# RelayExtension.net
KiCad netlist of a schematic drawn in Altium Designer
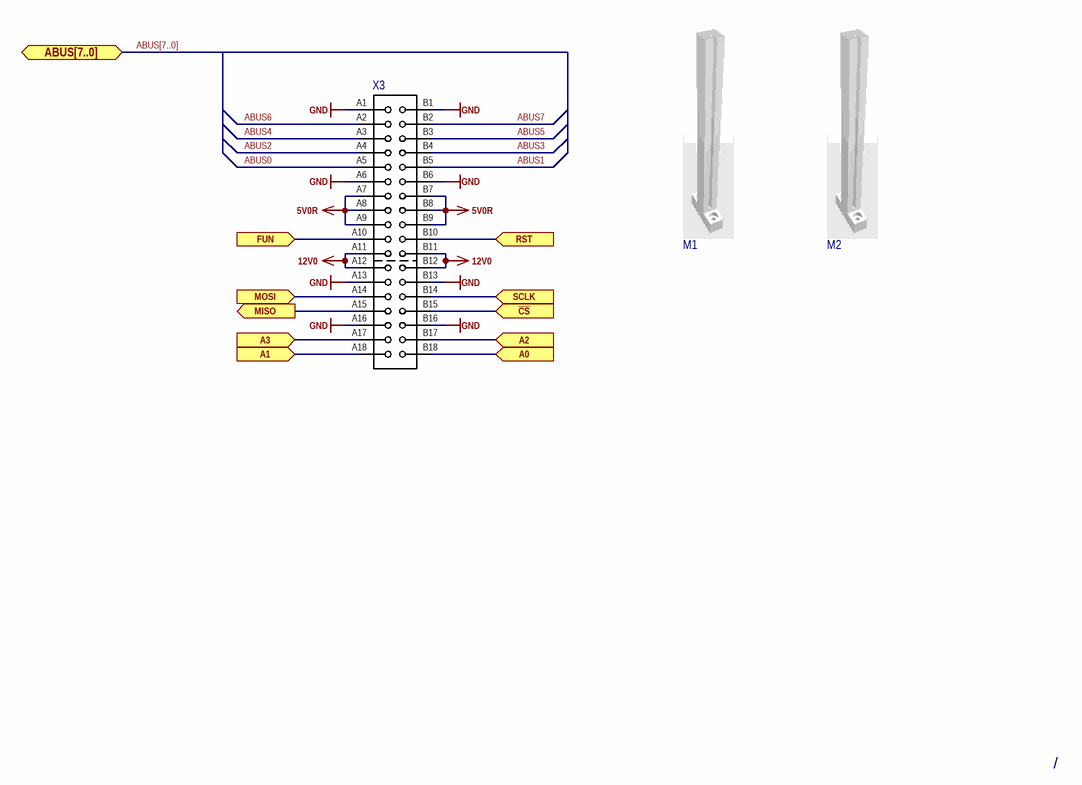
[diagram p0: RelayExtension.SchDoc]

(export (version "E")
  (design (tool "Eeschema 10.0.6"))
  (components
    (comp (ref "M1")
      (value "M")
      (footprint "Support Post")
      (description "Support Post")
      (fields (field (name "13. CREATED DATE/NAME") "??? / Hören"))
      (libsource (lib "PCB-Tester-Board") (part "Support Post"))
    )
    (comp (ref "M2")
      (value "M")
      (footprint "Support Post")
      (description "Support Post")
      (fields (field (name "13. CREATED DATE/NAME") "??? / Hören"))
      (libsource (lib "PCB-Tester-Board") (part "Support Post"))
    )
    (comp (ref "X3")
      (value "X")
      (footprint "PCIE-036-02-F-D-TH")
      (description "CONN PCI EXP FMALE 36POS 0.039")
      (fields
        (field (name "02. DISTRIBUTOR PART NUMBER") "SAM10625-ND")
        (field (name "07. MANUFACTURER  PART NUMBER") "PCIE-036-02-F-D-TH")
        (field (name "13. CREATED DATE/NAME") "??? / Hören")
      )
      (libsource (lib "Connectors") (part "PCIE-036-02-F-D-TH"))
    )
  )
  (nets
    (net (code "1") (name "/A0") (class "Default")
      (node (ref "X3") (pin "B18") (pinfunction "B18_B18") (pintype "passive"))
    )
    (net (code "2") (name "/A1") (class "Default")
      (node (ref "X3") (pin "A18") (pinfunction "A18_A18") (pintype "passive"))
    )
    (net (code "3") (name "/A2") (class "Default")
      (node (ref "X3") (pin "B17") (pinfunction "B17_B17") (pintype "passive"))
    )
    (net (code "4") (name "/A3") (class "Default")
      (node (ref "X3") (pin "A17") (pinfunction "A17_A17") (pintype "passive"))
    )
    (net (code "5") (name "/ABUS0") (class "Default")
      (node (ref "X3") (pin "A5") (pinfunction "A5_A5") (pintype "passive"))
    )
    (net (code "6") (name "/ABUS1") (class "Default")
      (node (ref "X3") (pin "B5") (pinfunction "B5_B5") (pintype "passive"))
    )
    (net (code "7") (name "/ABUS2") (class "Default")
      (node (ref "X3") (pin "A4") (pinfunction "A4_A4") (pintype "passive"))
    )
    (net (code "8") (name "/ABUS3") (class "Default")
      (node (ref "X3") (pin "B4") (pinfunction "B4_B4") (pintype "passive"))
    )
    (net (code "9") (name "/ABUS4") (class "Default")
      (node (ref "X3") (pin "A3") (pinfunction "A3_A3") (pintype "passive"))
    )
    (net (code "10") (name "/ABUS5") (class "Default")
      (node (ref "X3") (pin "B3") (pinfunction "B3_B3") (pintype "passive"))
    )
    (net (code "11") (name "/ABUS6") (class "Default")
      (node (ref "X3") (pin "A2") (pinfunction "A2_A2") (pintype "passive"))
    )
    (net (code "12") (name "/ABUS7") (class "Default")
      (node (ref "X3") (pin "B2") (pinfunction "B2_B2") (pintype "passive"))
    )
    (net (code "14") (name "/CS") (class "Default")
      (node (ref "X3") (pin "B15") (pinfunction "B15_B15") (pintype "passive"))
    )
    (net (code "15") (name "/FUN") (class "Default")
      (node (ref "X3") (pin "A10") (pinfunction "A10_A10") (pintype "passive"))
    )
    (net (code "16") (name "/MISO") (class "Default")
      (node (ref "X3") (pin "A15") (pinfunction "A15_A15") (pintype "passive"))
    )
    (net (code "17") (name "/MOSI") (class "Default")
      (node (ref "X3") (pin "A14") (pinfunction "A14_A14") (pintype "passive"))
    )
    (net (code "18") (name "/RST") (class "Default")
      (node (ref "X3") (pin "B10") (pinfunction "B10_B10") (pintype "passive"))
    )
    (net (code "19") (name "/SCLK") (class "Default")
      (node (ref "X3") (pin "B14") (pinfunction "B14_B14") (pintype "passive"))
    )
    (net (code "20") (name "5V0R") (class "Default")
      (node (ref "X3") (pin "A7") (pinfunction "A7_A7") (pintype "passive"))
      (node (ref "X3") (pin "A8") (pinfunction "A8_A8") (pintype "passive"))
      (node (ref "X3") (pin "A9") (pinfunction "A9_A9") (pintype "passive"))
      (node (ref "X3") (pin "B7") (pinfunction "B7_B7") (pintype "passive"))
      (node (ref "X3") (pin "B8") (pinfunction "B8_B8") (pintype "passive"))
      (node (ref "X3") (pin "B9") (pinfunction "B9_B9") (pintype "passive"))
    )
    (net (code "21") (name "12V0") (class "Default")
      (node (ref "X3") (pin "A11") (pinfunction "A11_A11") (pintype "passive"))
      (node (ref "X3") (pin "A12") (pinfunction "A12_A12") (pintype "passive"))
      (node (ref "X3") (pin "B11") (pinfunction "B11_B11") (pintype "passive"))
      (node (ref "X3") (pin "B12") (pinfunction "B12_B12") (pintype "passive"))
    )
    (net (code "22") (name "GND") (class "Default")
      (node (ref "X3") (pin "A1") (pinfunction "A1_A1") (pintype "passive"))
      (node (ref "X3") (pin "A13") (pinfunction "A13_A13") (pintype "passive"))
      (node (ref "X3") (pin "A16") (pinfunction "A16_A16") (pintype "passive"))
      (node (ref "X3") (pin "A6") (pinfunction "A6_A6") (pintype "passive"))
      (node (ref "X3") (pin "B1") (pinfunction "B1_B1") (pintype "passive"))
      (node (ref "X3") (pin "B13") (pinfunction "B13_B13") (pintype "passive"))
      (node (ref "X3") (pin "B16") (pinfunction "B16_B16") (pintype "passive"))
      (node (ref "X3") (pin "B6") (pinfunction "B6_B6") (pintype "passive"))
    )
  )
)
